# v2_0.net
KiCad netlist of a schematic drawn in Altium Designer
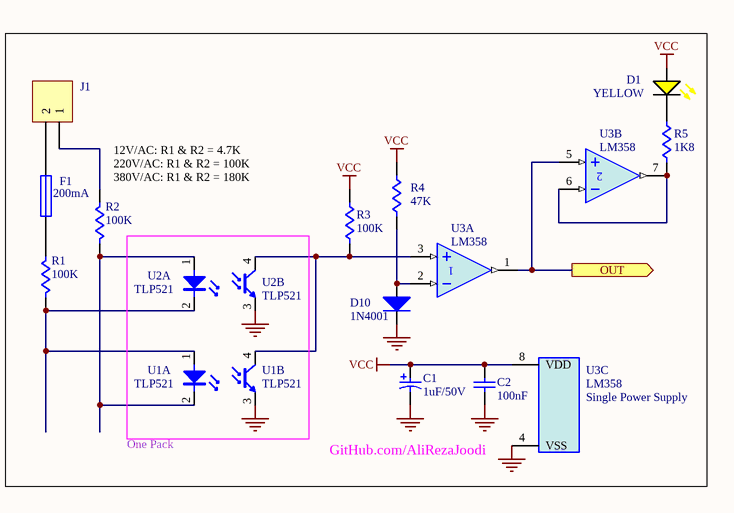
[diagram p0: v2.0.SchDoc]

(export (version "E")
  (design (tool "Eeschema 10.0.6"))
  (components
    (comp (ref "C1")
      (value "1uF/50V")
      (footprint "C_THD_EL_(P2.54-D6-H11)")
      (description "Capacitor, Electrolytic")
      (libsource (lib "Passive") (part "Capacitor_Electrolytic"))
    )
    (comp (ref "C2")
      (value "100nF")
      (footprint "C_THD_CER_(P2.54-D3.5-T1.5)")
      (description "Capacitor, Ceramic Multilayer")
      (libsource (lib "Passive") (part "Capacitor_Ceramic"))
    )
    (comp (ref "D1")
      (value "YELLOW")
      (footprint "LED_THD_5MM_YELLOW")
      (description "LED, Yellow")
      (fields (field (name "MANUFACTURER") "Generic Components") (field (name "PUBLISHER") "Altium Limited"))
      (libsource (lib "Display") (part "LED_YELLOW"))
    )
    (comp (ref "D10")
      (value "1N4001")
      (footprint "DIODE-0.4")
      (description "Default Diode")
      (fields (field (name "MANUFACTURER") "Generic Components") (field (name "PUBLISHER") "Altium Limited"))
      (libsource (lib "Miscellaneous Devices") (part "Diode"))
    )
    (comp (ref "F1")
      (value "200mA")
      (footprint "PIN-W2/E2.8")
      (description "Fuse")
      (fields (field (name "PUBLISHER") "Altium Limited"))
      (libsource (lib "Miscellaneous Devices") (part "Fuse 1"))
    )
    (comp (ref "J1")
      (value "Header 2")
      (footprint "Fonics_2PIN_1")
      (description "Header, 2-Pin")
      (fields (field (name "PUBLISHER") "Altium Limited"))
      (libsource (lib "Miscellaneous Connectors") (part "Header 2"))
    )
    (comp (ref "R1")
      (value "100K")
      (footprint "AXIAL-0.4")
      (description "Resistor")
      (fields
        (field (name "MANUFACTURER") "Generic Components")
        (field (name "Comment") "Res1")
        (field (name "PUBLISHER") "Altium Limited")
      )
      (libsource (lib "Miscellaneous Devices") (part "Res1"))
    )
    (comp (ref "R2")
      (value "100K")
      (footprint "AXIAL-0.4")
      (description "Resistor")
      (fields
        (field (name "MANUFACTURER") "Generic Components")
        (field (name "Comment") "Res1")
        (field (name "PUBLISHER") "Altium Limited")
      )
      (libsource (lib "Miscellaneous Devices") (part "Res1"))
    )
    (comp (ref "R3")
      (value "100K")
      (footprint "AXIAL-0.4")
      (description "Resistor")
      (fields
        (field (name "MANUFACTURER") "Generic Components")
        (field (name "Comment") "Res1")
        (field (name "PUBLISHER") "Altium Limited")
      )
      (libsource (lib "Miscellaneous Devices") (part "Res1"))
    )
    (comp (ref "R4")
      (value "47K")
      (footprint "AXIAL-0.4")
      (description "Resistor")
      (fields
        (field (name "MANUFACTURER") "Generic Components")
        (field (name "Comment") "Res1")
        (field (name "PUBLISHER") "Altium Limited")
      )
      (libsource (lib "Miscellaneous Devices") (part "Res1"))
    )
    (comp (ref "R5")
      (value "1K8")
      (footprint "AXIAL-0.4")
      (description "Resistor")
      (fields (field (name "MANUFACTURER") "Generic Components") (field (name "PUBLISHER") "Altium Limited"))
      (libsource (lib "Miscellaneous Devices") (part "Res1"))
    )
    (comp (ref "U1")
      (value "TLP521")
      (footprint "DIP-4")
      (fields (field (name "Comment") "Optoisolator") (field (name "PUBLISHER") "Altium Limited"))
      (libsource (lib "my Libraries") (part "Optoisolator"))
    )
    (comp (ref "U2")
      (value "TLP521")
      (footprint "DIP-4")
      (fields (field (name "Comment") "Optoisolator") (field (name "PUBLISHER") "Altium Limited"))
      (libsource (lib "my Libraries") (part "Optoisolator"))
    )
    (comp (ref "U3")
      (value "LM358")
      (footprint "DIP_8")
      (description "Dual Low-Power Operational Amplifier")
      (fields (field (name "PUBLISHER") "Altium Limited"))
      (libsource (lib "Op-Amp") (part "LM358"))
    )
  )
  (nets
    (net (code "1") (name "/OUT") (class "Default")
      (node (ref "U3") (pin "1") (pinfunction "OUT_1") (pintype "output"))
      (node (ref "U3") (pin "5") (pinfunction "IN+_5") (pintype "input"))
    )
    (net (code "2") (name "GND") (class "Default")
      (node (ref "C1") (pin "2") (pinfunction "2_2") (pintype "passive"))
      (node (ref "C2") (pin "2") (pinfunction "2_2") (pintype "passive"))
      (node (ref "D10") (pin "2") (pinfunction "K_2") (pintype "passive"))
      (node (ref "U1") (pin "3") (pinfunction "E_3") (pintype "passive"))
      (node (ref "U2") (pin "3") (pinfunction "E_3") (pintype "passive"))
      (node (ref "U3") (pin "4") (pinfunction "VSS_4") (pintype "power_in"))
    )
    (net (code "3") (name "Net-(D1-K)") (class "Default")
      (node (ref "D1") (pin "2") (pinfunction "K_2") (pintype "passive"))
      (node (ref "R5") (pin "2") (pinfunction "2_2") (pintype "passive"))
    )
    (net (code "4") (name "Net-(D10-A)") (class "Default")
      (node (ref "D10") (pin "1") (pinfunction "A_1") (pintype "passive"))
      (node (ref "R4") (pin "2") (pinfunction "2_2") (pintype "passive"))
      (node (ref "U3") (pin "2") (pinfunction "IN-_2") (pintype "input"))
    )
    (net (code "5") (name "Net-(F1-Pad1)") (class "Default")
      (node (ref "F1") (pin "1") (pinfunction "1_1") (pintype "passive"))
      (node (ref "R1") (pin "1") (pinfunction "1_1") (pintype "passive"))
    )
    (net (code "6") (name "Net-(F1-Pad2)") (class "Default")
      (node (ref "F1") (pin "2") (pinfunction "2_2") (pintype "passive"))
      (node (ref "J1") (pin "2") (pinfunction "2_2") (pintype "passive"))
    )
    (net (code "7") (name "Net-(J1-Pad1)") (class "Default")
      (node (ref "J1") (pin "1") (pinfunction "1_1") (pintype "passive"))
      (node (ref "R2") (pin "1") (pinfunction "1_1") (pintype "passive"))
    )
    (net (code "8") (name "Net-(U1A-A)") (class "Default")
      (node (ref "R1") (pin "2") (pinfunction "2_2") (pintype "passive"))
      (node (ref "U1") (pin "1") (pinfunction "A_1") (pintype "power_in"))
      (node (ref "U2") (pin "2") (pinfunction "K_2") (pintype "power_in"))
    )
    (net (code "9") (name "Net-(U1A-K)") (class "Default")
      (node (ref "R2") (pin "2") (pinfunction "2_2") (pintype "passive"))
      (node (ref "U1") (pin "2") (pinfunction "K_2") (pintype "power_in"))
      (node (ref "U2") (pin "1") (pinfunction "A_1") (pintype "power_in"))
    )
    (net (code "10") (name "Net-(U1B-C)") (class "Default")
      (node (ref "R3") (pin "2") (pinfunction "2_2") (pintype "passive"))
      (node (ref "U1") (pin "4") (pinfunction "C_4") (pintype "passive"))
      (node (ref "U2") (pin "4") (pinfunction "C_4") (pintype "passive"))
      (node (ref "U3") (pin "3") (pinfunction "IN+_3") (pintype "input"))
    )
    (net (code "11") (name "Net-(U3B-IN-)") (class "Default")
      (node (ref "R5") (pin "1") (pinfunction "1_1") (pintype "passive"))
      (node (ref "U3") (pin "6") (pinfunction "IN-_6") (pintype "input"))
      (node (ref "U3") (pin "7") (pinfunction "OUT_7") (pintype "output"))
    )
    (net (code "12") (name "VCC") (class "Default")
      (node (ref "C1") (pin "1") (pinfunction "1_1") (pintype "passive"))
      (node (ref "C2") (pin "1") (pinfunction "1_1") (pintype "passive"))
      (node (ref "D1") (pin "1") (pinfunction "A_1") (pintype "passive"))
      (node (ref "R3") (pin "1") (pinfunction "1_1") (pintype "passive"))
      (node (ref "R4") (pin "1") (pinfunction "1_1") (pintype "passive"))
      (node (ref "U3") (pin "8") (pinfunction "VDD_8") (pintype "passive"))
    )
  )
)
